# d11_usb_mini.net
KiCad netlist of a schematic drawn in EAGLE
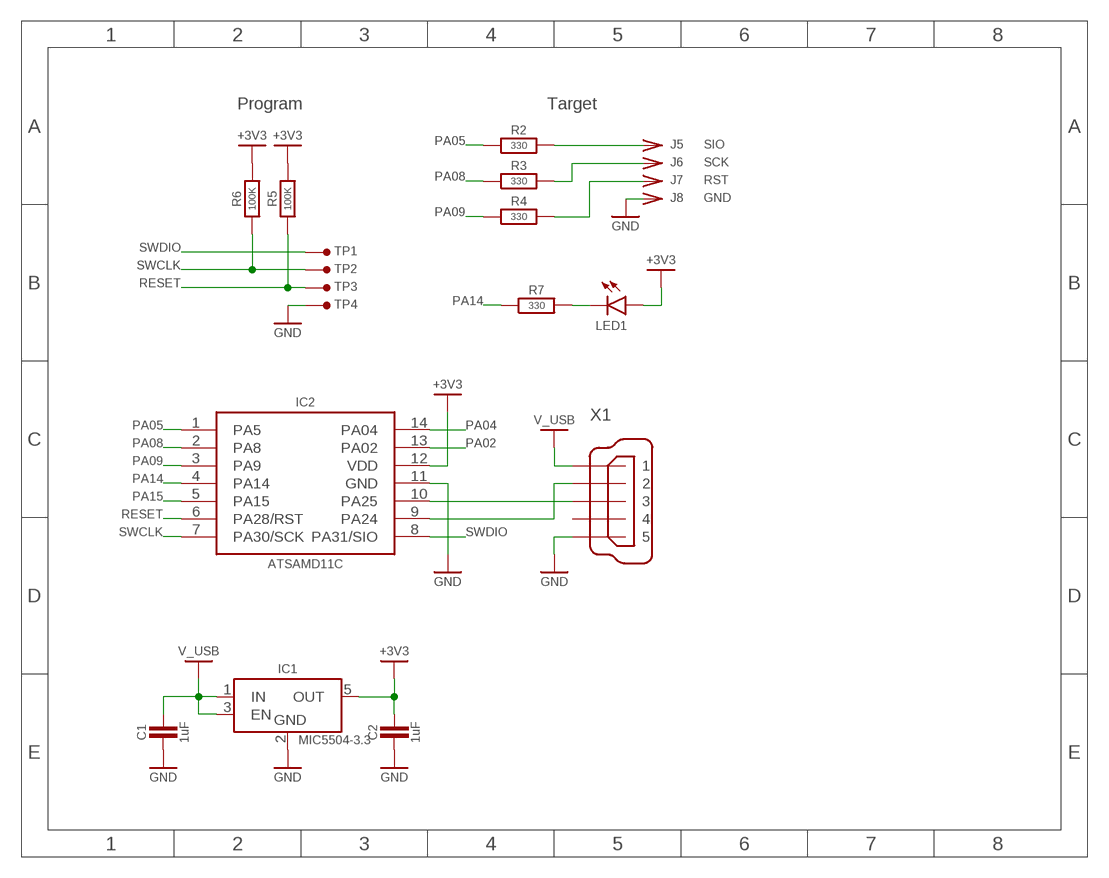
[diagram p0: schematic, sheet 1]

(export (version "E")
  (design (tool "Eeschema 10.0.6"))
  (components
    (comp (ref "C1")
      (value "1uF")
      (footprint "eagle-import:SMD0603")
      (libsource (lib "eagle-import") (part "C-0603"))
    )
    (comp (ref "C2")
      (value "1uF")
      (footprint "eagle-import:SMD0603")
      (libsource (lib "eagle-import") (part "C-0603"))
    )
    (comp (ref "IC1")
      (value "MIC5504-3.3")
      (footprint "eagle-import:SOT23-5")
      (libsource (lib "eagle-import") (part "MIC5504-SOT23-5"))
    )
    (comp (ref "IC2")
      (value "ATSAMD11C")
      (footprint "eagle-import:SO-14")
      (libsource (lib "eagle-import") (part "ATSAMD11C"))
    )
    (comp (ref "J5")
      (value "SIO")
      (footprint "eagle-import:PIN-TH")
      (libsource (lib "eagle-import") (part "CONN-SINGLE-TH"))
    )
    (comp (ref "J6")
      (value "SCK")
      (footprint "eagle-import:PIN-TH")
      (libsource (lib "eagle-import") (part "CONN-SINGLE-TH"))
    )
    (comp (ref "J7")
      (value "RST")
      (footprint "eagle-import:PIN-TH")
      (libsource (lib "eagle-import") (part "CONN-SINGLE-TH"))
    )
    (comp (ref "J8")
      (value "GND")
      (footprint "eagle-import:PIN-TH")
      (libsource (lib "eagle-import") (part "CONN-SINGLE-TH"))
    )
    (comp (ref "LED1")
      (value "LED_SMDLED_0603")
      (footprint "eagle-import:SMD0603")
      (libsource (lib "eagle-import") (part "LED_SMDLED_0603"))
    )
    (comp (ref "R2")
      (value "330")
      (footprint "eagle-import:SMD0603")
      (libsource (lib "eagle-import") (part "R-0603"))
    )
    (comp (ref "R3")
      (value "330")
      (footprint "eagle-import:SMD0603")
      (libsource (lib "eagle-import") (part "R-0603"))
    )
    (comp (ref "R4")
      (value "330")
      (footprint "eagle-import:SMD0603")
      (libsource (lib "eagle-import") (part "R-0603"))
    )
    (comp (ref "R5")
      (value "100K")
      (footprint "eagle-import:SMD0603")
      (libsource (lib "eagle-import") (part "R-0603"))
    )
    (comp (ref "R6")
      (value "100K")
      (footprint "eagle-import:SMD0603")
      (libsource (lib "eagle-import") (part "R-0603"))
    )
    (comp (ref "R7")
      (value "330")
      (footprint "eagle-import:SMD0603")
      (libsource (lib "eagle-import") (part "R-0603"))
    )
    (comp (ref "TP1")
      (value "SIO")
      (footprint "eagle-import:TP-1.27MM")
      (libsource (lib "eagle-import") (part "TEST-POINT-1.27MM"))
    )
    (comp (ref "TP2")
      (value "TEST-POINT-1.27MM")
      (footprint "eagle-import:TP-1.27MM")
      (libsource (lib "eagle-import") (part "TEST-POINT-1.27MM"))
    )
    (comp (ref "TP3")
      (value "TEST-POINT-1.27MM")
      (footprint "eagle-import:TP-1.27MM")
      (libsource (lib "eagle-import") (part "TEST-POINT-1.27MM"))
    )
    (comp (ref "TP4")
      (value "TEST-POINT-1.27MM")
      (footprint "eagle-import:TP-1.27MM")
      (libsource (lib "eagle-import") (part "TEST-POINT-1.27MM"))
    )
    (comp (ref "X1")
      (value "MINI-USB-32005-201")
      (footprint "eagle-import:32005-201")
      (libsource (lib "eagle-import") (part "MINI-USB-32005-201"))
    )
  )
  (nets
    (net (code "1") (name "+3V3") (class "Default")
      (node (ref "C2") (pin "2") (pinfunction "2_2") (pintype "passive"))
      (node (ref "IC1") (pin "5") (pinfunction "OUT_5") (pintype "power_in"))
      (node (ref "IC2") (pin "12") (pinfunction "VDD_12") (pintype "bidirectional"))
      (node (ref "LED1") (pin "1") (pinfunction "A_1") (pintype "passive"))
      (node (ref "R5") (pin "2") (pinfunction "2_2") (pintype "passive"))
      (node (ref "R6") (pin "2") (pinfunction "2_2") (pintype "passive"))
    )
    (net (code "2") (name "/PA02") (class "Default")
      (node (ref "IC2") (pin "13") (pinfunction "PA02_13") (pintype "bidirectional"))
    )
    (net (code "3") (name "/PA04") (class "Default")
      (node (ref "IC2") (pin "14") (pinfunction "PA04_14") (pintype "bidirectional"))
    )
    (net (code "4") (name "/PA05") (class "Default")
      (node (ref "IC2") (pin "1") (pinfunction "PA5_1") (pintype "bidirectional"))
      (node (ref "R2") (pin "1") (pinfunction "1_1") (pintype "passive"))
    )
    (net (code "5") (name "/PA08") (class "Default")
      (node (ref "IC2") (pin "2") (pinfunction "PA8_2") (pintype "bidirectional"))
      (node (ref "R3") (pin "1") (pinfunction "1_1") (pintype "passive"))
    )
    (net (code "6") (name "/PA09") (class "Default")
      (node (ref "IC2") (pin "3") (pinfunction "PA9_3") (pintype "bidirectional"))
      (node (ref "R4") (pin "1") (pinfunction "1_1") (pintype "passive"))
    )
    (net (code "7") (name "/PA14") (class "Default")
      (node (ref "IC2") (pin "4") (pinfunction "PA14_4") (pintype "bidirectional"))
      (node (ref "R7") (pin "1") (pinfunction "1_1") (pintype "passive"))
    )
    (net (code "8") (name "/PA15") (class "Default")
      (node (ref "IC2") (pin "5") (pinfunction "PA15_5") (pintype "bidirectional"))
    )
    (net (code "9") (name "/RESET") (class "Default")
      (node (ref "IC2") (pin "6") (pinfunction "PA28/RST_6") (pintype "bidirectional"))
      (node (ref "R5") (pin "1") (pinfunction "1_1") (pintype "passive"))
      (node (ref "TP3") (pin "1") (pinfunction "1_1") (pintype "passive"))
    )
    (net (code "10") (name "/SWCLK") (class "Default")
      (node (ref "IC2") (pin "7") (pinfunction "PA30/SCK_7") (pintype "bidirectional"))
      (node (ref "R6") (pin "1") (pinfunction "1_1") (pintype "passive"))
      (node (ref "TP2") (pin "1") (pinfunction "1_1") (pintype "passive"))
    )
    (net (code "11") (name "/SWDIO") (class "Default")
      (node (ref "IC2") (pin "8") (pinfunction "PA31/SIO_8") (pintype "bidirectional"))
      (node (ref "TP1") (pin "1") (pinfunction "1_1") (pintype "passive"))
    )
    (net (code "12") (name "GND") (class "Default")
      (node (ref "C1") (pin "1") (pinfunction "1_1") (pintype "passive"))
      (node (ref "C2") (pin "1") (pinfunction "1_1") (pintype "passive"))
      (node (ref "IC1") (pin "2") (pinfunction "GND_2") (pintype "power_in"))
      (node (ref "IC2") (pin "11") (pinfunction "GND_11") (pintype "bidirectional"))
      (node (ref "J8") (pin "1") (pinfunction "1_1") (pintype "passive"))
      (node (ref "TP4") (pin "1") (pinfunction "1_1") (pintype "passive"))
      (node (ref "X1") (pin "5") (pinfunction "5_5") (pintype "passive"))
    )
    (net (code "13") (name "Net-(IC2-PA24)") (class "Default")
      (node (ref "IC2") (pin "9") (pinfunction "PA24_9") (pintype "bidirectional"))
      (node (ref "X1") (pin "2") (pinfunction "2_2") (pintype "passive"))
    )
    (net (code "14") (name "Net-(IC2-PA25)") (class "Default")
      (node (ref "IC2") (pin "10") (pinfunction "PA25_10") (pintype "bidirectional"))
      (node (ref "X1") (pin "3") (pinfunction "3_3") (pintype "passive"))
    )
    (net (code "15") (name "Net-(J5-Pad1)") (class "Default")
      (node (ref "J5") (pin "1") (pinfunction "1_1") (pintype "passive"))
      (node (ref "R2") (pin "2") (pinfunction "2_2") (pintype "passive"))
    )
    (net (code "16") (name "Net-(J6-Pad1)") (class "Default")
      (node (ref "J6") (pin "1") (pinfunction "1_1") (pintype "passive"))
      (node (ref "R3") (pin "2") (pinfunction "2_2") (pintype "passive"))
    )
    (net (code "17") (name "Net-(J7-Pad1)") (class "Default")
      (node (ref "J7") (pin "1") (pinfunction "1_1") (pintype "passive"))
      (node (ref "R4") (pin "2") (pinfunction "2_2") (pintype "passive"))
    )
    (net (code "18") (name "Net-(LED1-C)") (class "Default")
      (node (ref "LED1") (pin "2") (pinfunction "C_2") (pintype "passive"))
      (node (ref "R7") (pin "2") (pinfunction "2_2") (pintype "passive"))
    )
    (net (code "19") (name "V_USB") (class "Default")
      (node (ref "C1") (pin "2") (pinfunction "2_2") (pintype "passive"))
      (node (ref "IC1") (pin "1") (pinfunction "IN_1") (pintype "power_in"))
      (node (ref "IC1") (pin "3") (pinfunction "EN_3") (pintype "input"))
      (node (ref "X1") (pin "1") (pinfunction "1_1") (pintype "passive"))
    )
    (net (code "20") (name "unconnected-(X1-Pad4)") (class "Default")
      (node (ref "X1") (pin "4") (pinfunction "4_4") (pintype "passive"))
    )
  )
)
